# s1mple.net
KiCad netlist of a schematic drawn in Altium Designer
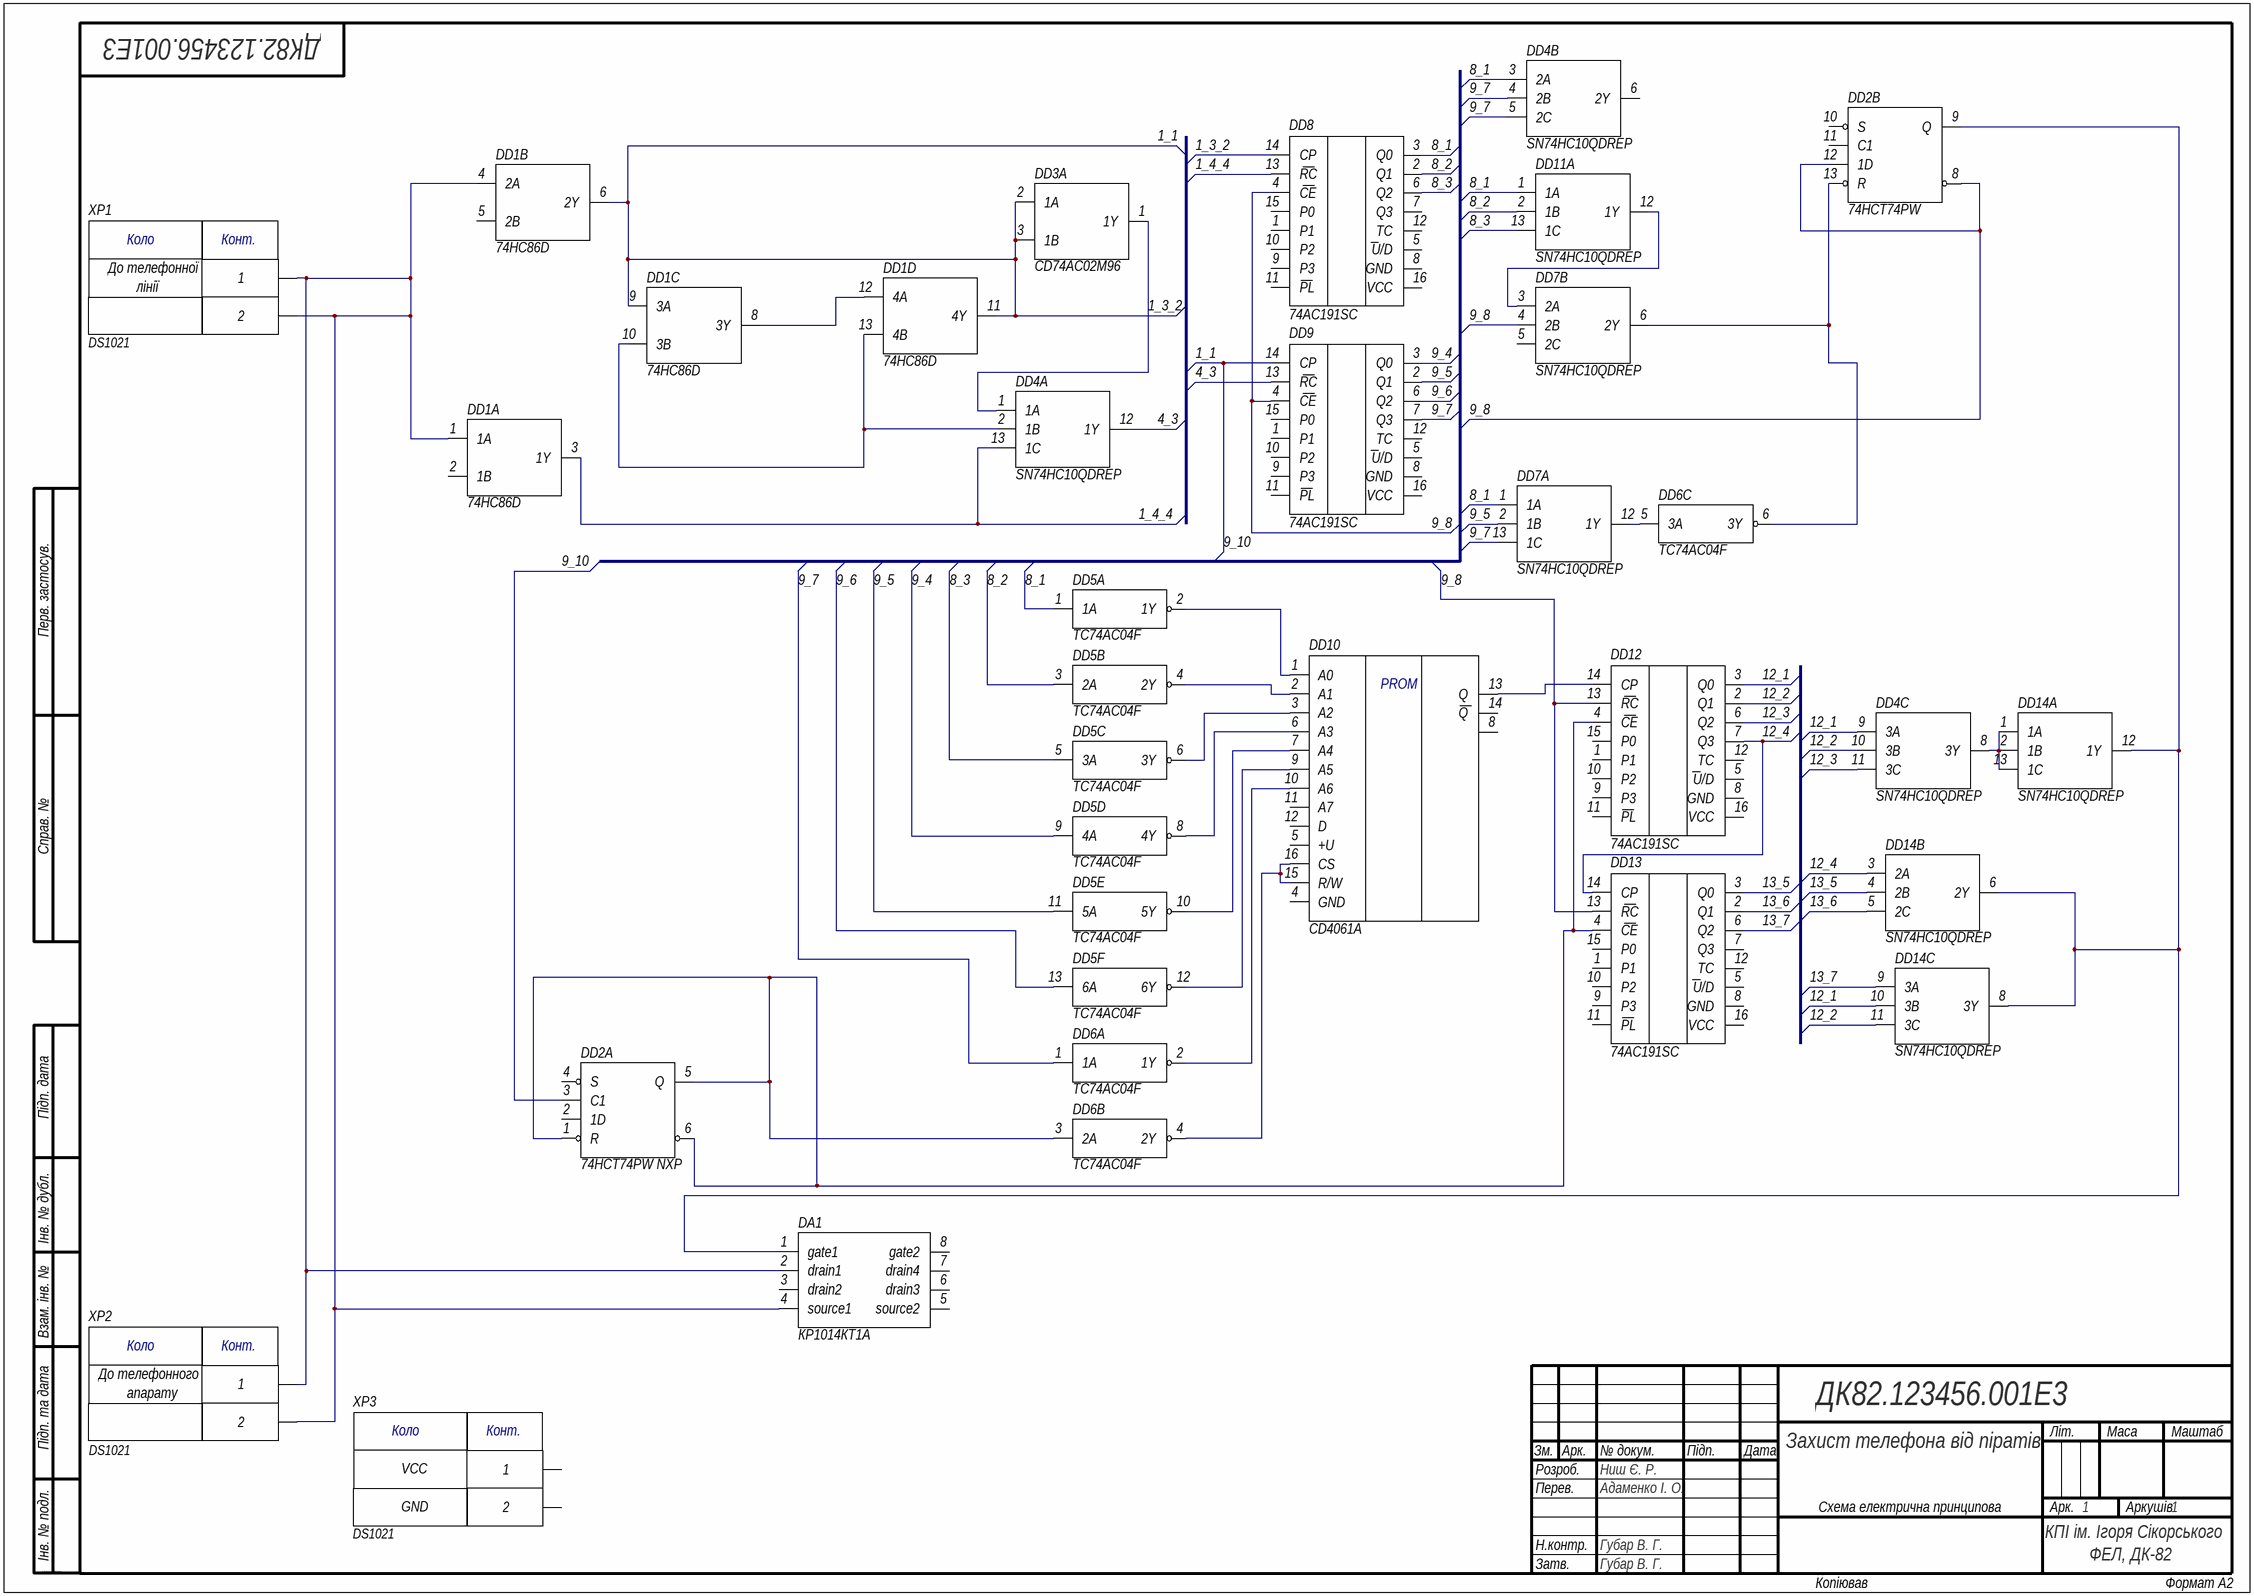
[diagram p0: s1mple.SchDoc]

(export (version "E")
  (design (tool "Eeschema 10.0.6"))
  (components
    (comp (ref "DA1")
      (value "КР1014КТ1А Электроника и связь")
      (footprint "DIP8")
      (fields (field (name "NAME") "КР1014КТ1А") (field (name "MANUFACTURER") "Электроника и связь"))
      (libsource (lib "Schlib1") (part "КР1014КТ1А"))
    )
    (comp (ref "DD1")
      (value "74HC86D Philips")
      (footprint "SOIC-14")
      (description "OR")
      (fields (field (name "NAME") "74HC86D") (field (name "MANUFACTURER") "Philips"))
      (libsource (lib "Schlib1") (part "74HC86D"))
    )
    (comp (ref "DD2")
      (value "74HCT74PW NXP")
      (footprint "TSSOP-14")
      (description "DUAL D FF POSEDG TRIG")
      (fields (field (name "MANUFACTURER") "NXP") (field (name "NAME") "74HCT74PW"))
      (libsource (lib "Schlib1") (part "74HCT74PW"))
    )
    (comp (ref "DD3")
      (value "CD74AC02M96 TI")
      (footprint "SOIC-14")
      (description "2-INPUT NOR GATE")
      (fields (field (name "NAME") "CD74AC02M96") (field (name "MANUFACTURER") "TI"))
      (libsource (lib "Schlib1") (part "CD74AC02M96"))
    )
    (comp (ref "DD4")
      (value "SN74HC10QDREP Texas Instruments")
      (footprint "SOIC-14")
      (description "3-INPUT NAND GATE")
      (fields (field (name "NAME") "SN74HC10QDREP") (field (name "MANUFACTURER") "Texas Instruments"))
      (libsource (lib "Schlib1") (part "SN74HC10QDREP"))
    )
    (comp (ref "DD5")
      (value "TC74AC04F Toshiba")
      (footprint "SOIC-14")
      (description "NOT")
      (fields (field (name "NAME") "TC74AC04F") (field (name "MANUFACTURER") "Toshiba"))
      (libsource (lib "Schlib1") (part "TC74AC04F"))
    )
    (comp (ref "DD6")
      (value "TC74AC04F Toshiba")
      (footprint "SOIC-14")
      (description "NOT")
      (fields (field (name "NAME") "TC74AC04F") (field (name "MANUFACTURER") "Toshiba"))
      (libsource (lib "Schlib1") (part "TC74AC04F"))
    )
    (comp (ref "DD7")
      (value "SN74HC10QDREP Texas Instruments")
      (footprint "SOIC-14")
      (description "3-INPUT NAND GATE")
      (fields (field (name "NAME") "SN74HC10QDREP") (field (name "MANUFACTURER") "Texas Instruments"))
      (libsource (lib "Schlib1") (part "SN74HC10QDREP"))
    )
    (comp (ref "DD8")
      (value "74AC191SC Fairchild")
      (footprint "SOIC-16")
      (description "Counter")
      (fields (field (name "NAME") "74AC191SC") (field (name "MANUFACTURER") "Fairchild"))
      (libsource (lib "Schlib1") (part "74AC191SC"))
    )
    (comp (ref "DD9")
      (value "74AC191SC Fairchild")
      (footprint "SOIC-16")
      (description "Counter")
      (fields (field (name "NAME") "74AC191SC") (field (name "MANUFACTURER") "Fairchild"))
      (libsource (lib "Schlib1") (part "74AC191SC"))
    )
    (comp (ref "DD10")
      (value "CD4061A NXP")
      (footprint "DIP16")
      (fields (field (name "NAME") "CD4061A") (field (name "MANUFACTURER") "NXP"))
      (libsource (lib "Schlib1") (part "CD4061A"))
    )
    (comp (ref "DD11")
      (value "SN74HC10QDREP Texas Instruments")
      (footprint "SOIC-14")
      (description "3-INPUT NAND GATE")
      (fields (field (name "NAME") "SN74HC10QDREP") (field (name "MANUFACTURER") "Texas Instruments"))
      (libsource (lib "Schlib1") (part "SN74HC10QDREP"))
    )
    (comp (ref "DD12")
      (value "74AC191SC Fairchild")
      (footprint "SOIC-16")
      (description "Counter")
      (fields (field (name "NAME") "74AC191SC") (field (name "MANUFACTURER") "Fairchild"))
      (libsource (lib "Schlib1") (part "74AC191SC"))
    )
    (comp (ref "DD13")
      (value "74AC191SC Fairchild")
      (footprint "SOIC-16")
      (description "Counter")
      (fields (field (name "NAME") "74AC191SC") (field (name "MANUFACTURER") "Fairchild"))
      (libsource (lib "Schlib1") (part "74AC191SC"))
    )
    (comp (ref "DD14")
      (value "SN74HC10QDREP Texas Instruments")
      (footprint "SOIC-14")
      (description "3-INPUT NAND GATE")
      (fields (field (name "NAME") "SN74HC10QDREP") (field (name "MANUFACTURER") "Texas Instruments"))
      (libsource (lib "Schlib1") (part "SN74HC10QDREP"))
    )
    (comp (ref "XP1")
      (value "DS1021 Ningbo Zhenqin Electronic")
      (footprint "PLS-2")
      (description "PLS-2_1x2")
      (fields (field (name "MANUFACTURER") "Ningbo Zhenqin Electronic") (field (name "NAME") "DS1021"))
      (libsource (lib "Schlib1") (part "DS1021"))
    )
    (comp (ref "XP2")
      (value "DS1021 Ningbo Zhenqin Electronic")
      (footprint "PLS-2")
      (description "PLS-2_1x2")
      (fields (field (name "MANUFACTURER") "Ningbo Zhenqin Electronic") (field (name "NAME") "DS1021"))
      (libsource (lib "Schlib1") (part "DS1021"))
    )
    (comp (ref "XP3")
      (value "DS1021 Ningbo Zhenqin Electronic")
      (footprint "PLS-2")
      (description "PLS-2_1x2")
      (fields (field (name "MANUFACTURER") "Ningbo Zhenqin Electronic") (field (name "NAME") "DS1021"))
      (libsource (lib "Schlib1") (part "DS1021"))
    )
  )
  (nets
    (net (code "1") (name "/1_1") (class "Default")
      (node (ref "DD1") (pin "11") (pinfunction "4Y_11") (pintype "passive"))
      (node (ref "DD1") (pin "6") (pinfunction "2Y_6") (pintype "passive"))
      (node (ref "DD1") (pin "9") (pinfunction "3A_9") (pintype "passive"))
      (node (ref "DD2") (pin "3") (pinfunction "C1_3") (pintype "passive"))
      (node (ref "DD3") (pin "1") (pinfunction "1Y_1") (pintype "passive"))
      (node (ref "DD3") (pin "2") (pinfunction "1A_2") (pintype "passive"))
      (node (ref "DD3") (pin "3") (pinfunction "1B_3") (pintype "passive"))
      (node (ref "DD4") (pin "1") (pinfunction "1A_1") (pintype "passive"))
      (node (ref "DD8") (pin "14") (pinfunction "CP_14") (pintype "passive"))
      (node (ref "DD9") (pin "14") (pinfunction "CP_14") (pintype "passive"))
    )
    (net (code "2") (name "/1_4_4") (class "Default")
      (node (ref "DD1") (pin "3") (pinfunction "1Y_3") (pintype "passive"))
      (node (ref "DD4") (pin "13") (pinfunction "1C_13") (pintype "passive"))
      (node (ref "DD8") (pin "13") (pinfunction "RC_13") (pintype "passive"))
    )
    (net (code "3") (name "/4_3") (class "Default")
      (node (ref "DD4") (pin "12") (pinfunction "1Y_12") (pintype "passive"))
      (node (ref "DD9") (pin "13") (pinfunction "RC_13") (pintype "passive"))
    )
    (net (code "4") (name "/8_1") (class "Default")
      (node (ref "DD11") (pin "1") (pinfunction "1A_1") (pintype "passive"))
      (node (ref "DD4") (pin "3") (pinfunction "2A_3") (pintype "passive"))
      (node (ref "DD5") (pin "1") (pinfunction "1A_1") (pintype "passive"))
      (node (ref "DD7") (pin "1") (pinfunction "1A_1") (pintype "passive"))
      (node (ref "DD8") (pin "3") (pinfunction "Q0_3") (pintype "passive"))
    )
    (net (code "5") (name "/8_2") (class "Default")
      (node (ref "DD11") (pin "2") (pinfunction "1B_2") (pintype "passive"))
      (node (ref "DD5") (pin "3") (pinfunction "2A_3") (pintype "passive"))
      (node (ref "DD8") (pin "2") (pinfunction "Q1_2") (pintype "passive"))
    )
    (net (code "6") (name "/8_3") (class "Default")
      (node (ref "DD11") (pin "13") (pinfunction "1C_13") (pintype "passive"))
      (node (ref "DD5") (pin "5") (pinfunction "3A_5") (pintype "passive"))
      (node (ref "DD8") (pin "6") (pinfunction "Q2_6") (pintype "passive"))
    )
    (net (code "7") (name "/9_4") (class "Default")
      (node (ref "DD5") (pin "9") (pinfunction "4A_9") (pintype "passive"))
      (node (ref "DD9") (pin "3") (pinfunction "Q0_3") (pintype "passive"))
    )
    (net (code "8") (name "/9_5") (class "Default")
      (node (ref "DD5") (pin "11") (pinfunction "5A_11") (pintype "passive"))
      (node (ref "DD7") (pin "2") (pinfunction "1B_2") (pintype "passive"))
      (node (ref "DD9") (pin "2") (pinfunction "Q1_2") (pintype "passive"))
    )
    (net (code "9") (name "/9_6") (class "Default")
      (node (ref "DD5") (pin "13") (pinfunction "6A_13") (pintype "passive"))
      (node (ref "DD9") (pin "6") (pinfunction "Q2_6") (pintype "passive"))
    )
    (net (code "10") (name "/9_7") (class "Default")
      (node (ref "DD4") (pin "4") (pinfunction "2B_4") (pintype "passive"))
      (node (ref "DD4") (pin "5") (pinfunction "2C_5") (pintype "passive"))
      (node (ref "DD6") (pin "1") (pinfunction "1A_1") (pintype "passive"))
      (node (ref "DD7") (pin "13") (pinfunction "1C_13") (pintype "passive"))
      (node (ref "DD9") (pin "7") (pinfunction "Q3_7") (pintype "passive"))
    )
    (net (code "11") (name "/9_8") (class "Default")
      (node (ref "DD12") (pin "13") (pinfunction "RC_13") (pintype "passive"))
      (node (ref "DD13") (pin "13") (pinfunction "RC_13") (pintype "passive"))
      (node (ref "DD2") (pin "12") (pinfunction "1D_12") (pintype "passive"))
      (node (ref "DD2") (pin "8") (pinfunction "Q_8") (pintype "passive"))
      (node (ref "DD7") (pin "4") (pinfunction "2B_4") (pintype "passive"))
      (node (ref "DD8") (pin "4") (pinfunction "CE_4") (pintype "passive"))
      (node (ref "DD9") (pin "4") (pinfunction "CE_4") (pintype "passive"))
    )
    (net (code "12") (name "/12_1") (class "Default")
      (node (ref "DD12") (pin "3") (pinfunction "Q0_3") (pintype "passive"))
      (node (ref "DD14") (pin "10") (pinfunction "3B_10") (pintype "passive"))
      (node (ref "DD4") (pin "9") (pinfunction "3A_9") (pintype "passive"))
    )
    (net (code "13") (name "/12_2") (class "Default")
      (node (ref "DD12") (pin "2") (pinfunction "Q1_2") (pintype "passive"))
      (node (ref "DD14") (pin "11") (pinfunction "3C_11") (pintype "passive"))
      (node (ref "DD4") (pin "10") (pinfunction "3B_10") (pintype "passive"))
    )
    (net (code "14") (name "/12_3") (class "Default")
      (node (ref "DD12") (pin "6") (pinfunction "Q2_6") (pintype "passive"))
      (node (ref "DD4") (pin "11") (pinfunction "3C_11") (pintype "passive"))
    )
    (net (code "15") (name "/12_4") (class "Default")
      (node (ref "DD12") (pin "7") (pinfunction "Q3_7") (pintype "passive"))
      (node (ref "DD13") (pin "14") (pinfunction "CP_14") (pintype "passive"))
      (node (ref "DD14") (pin "3") (pinfunction "2A_3") (pintype "passive"))
    )
    (net (code "16") (name "/13_5") (class "Default")
      (node (ref "DD13") (pin "3") (pinfunction "Q0_3") (pintype "passive"))
      (node (ref "DD14") (pin "4") (pinfunction "2B_4") (pintype "passive"))
    )
    (net (code "17") (name "/13_6") (class "Default")
      (node (ref "DD13") (pin "2") (pinfunction "Q1_2") (pintype "passive"))
      (node (ref "DD14") (pin "5") (pinfunction "2C_5") (pintype "passive"))
    )
    (net (code "18") (name "/13_7") (class "Default")
      (node (ref "DD13") (pin "6") (pinfunction "Q2_6") (pintype "passive"))
      (node (ref "DD14") (pin "9") (pinfunction "3A_9") (pintype "passive"))
    )
    (net (code "19") (name "Net-(DA1-drain1)") (class "Default")
      (node (ref "DA1") (pin "2") (pinfunction "drain1_2") (pintype "passive"))
      (node (ref "DA1") (pin "4") (pinfunction "source1_4") (pintype "passive"))
      (node (ref "DD1") (pin "1") (pinfunction "1A_1") (pintype "passive"))
      (node (ref "DD1") (pin "4") (pinfunction "2A_4") (pintype "passive"))
      (node (ref "XP1") (pin "1") (pinfunction "1_1") (pintype "passive"))
      (node (ref "XP1") (pin "2") (pinfunction "2_2") (pintype "passive"))
      (node (ref "XP2") (pin "1") (pinfunction "1_1") (pintype "passive"))
      (node (ref "XP2") (pin "2") (pinfunction "2_2") (pintype "passive"))
    )
    (net (code "20") (name "Net-(DA1-gate1)") (class "Default")
      (node (ref "DA1") (pin "1") (pinfunction "gate1_1") (pintype "passive"))
      (node (ref "DD14") (pin "12") (pinfunction "1Y_12") (pintype "passive"))
      (node (ref "DD14") (pin "6") (pinfunction "2Y_6") (pintype "passive"))
      (node (ref "DD14") (pin "8") (pinfunction "3Y_8") (pintype "passive"))
      (node (ref "DD2") (pin "9") (pinfunction "Q_9") (pintype "passive"))
    )
    (net (code "21") (name "Net-(DD1C-3B)") (class "Default")
      (node (ref "DD1") (pin "10") (pinfunction "3B_10") (pintype "passive"))
      (node (ref "DD1") (pin "13") (pinfunction "4B_13") (pintype "passive"))
      (node (ref "DD4") (pin "2") (pinfunction "1B_2") (pintype "passive"))
    )
    (net (code "22") (name "Net-(DD1C-3Y)") (class "Default")
      (node (ref "DD1") (pin "12") (pinfunction "4A_12") (pintype "passive"))
      (node (ref "DD1") (pin "8") (pinfunction "3Y_8") (pintype "passive"))
    )
    (net (code "23") (name "Net-(DD2B-R)") (class "Default")
      (node (ref "DD2") (pin "13") (pinfunction "R_13") (pintype "passive"))
      (node (ref "DD6") (pin "6") (pinfunction "3Y_6") (pintype "passive"))
      (node (ref "DD7") (pin "6") (pinfunction "2Y_6") (pintype "passive"))
    )
    (net (code "24") (name "Net-(DD6C-3A)") (class "Default")
      (node (ref "DD6") (pin "5") (pinfunction "3A_5") (pintype "passive"))
      (node (ref "DD7") (pin "12") (pinfunction "1Y_12") (pintype "passive"))
    )
    (net (code "25") (name "Net-(DD10-A0)") (class "Default")
      (node (ref "DD10") (pin "1") (pinfunction "A0_1") (pintype "passive"))
      (node (ref "DD5") (pin "2") (pinfunction "1Y_2") (pintype "passive"))
    )
    (net (code "26") (name "Net-(DD10-A1)") (class "Default")
      (node (ref "DD10") (pin "2") (pinfunction "A1_2") (pintype "passive"))
      (node (ref "DD5") (pin "4") (pinfunction "2Y_4") (pintype "passive"))
    )
    (net (code "27") (name "Net-(DD10-A2)") (class "Default")
      (node (ref "DD10") (pin "3") (pinfunction "A2_3") (pintype "passive"))
      (node (ref "DD5") (pin "6") (pinfunction "3Y_6") (pintype "passive"))
    )
    (net (code "28") (name "Net-(DD10-A3)") (class "Default")
      (node (ref "DD10") (pin "6") (pinfunction "A3_6") (pintype "passive"))
      (node (ref "DD5") (pin "8") (pinfunction "4Y_8") (pintype "passive"))
    )
    (net (code "29") (name "Net-(DD10-A4)") (class "Default")
      (node (ref "DD10") (pin "7") (pinfunction "A4_7") (pintype "passive"))
      (node (ref "DD5") (pin "10") (pinfunction "5Y_10") (pintype "passive"))
    )
    (net (code "30") (name "Net-(DD10-A5)") (class "Default")
      (node (ref "DD10") (pin "9") (pinfunction "A5_9") (pintype "passive"))
      (node (ref "DD5") (pin "12") (pinfunction "6Y_12") (pintype "passive"))
    )
    (net (code "31") (name "Net-(DD10-A6)") (class "Default")
      (node (ref "DD10") (pin "10") (pinfunction "A6_10") (pintype "passive"))
      (node (ref "DD6") (pin "2") (pinfunction "1Y_2") (pintype "passive"))
    )
    (net (code "32") (name "Net-(DD10-CS)") (class "Default")
      (node (ref "DD10") (pin "15") (pinfunction "R/W_15") (pintype "passive"))
      (node (ref "DD10") (pin "16") (pinfunction "CS_16") (pintype "passive"))
      (node (ref "DD6") (pin "4") (pinfunction "2Y_4") (pintype "passive"))
    )
    (net (code "33") (name "Net-(DD11A-1Y)") (class "Default")
      (node (ref "DD11") (pin "12") (pinfunction "1Y_12") (pintype "passive"))
      (node (ref "DD7") (pin "3") (pinfunction "2A_3") (pintype "passive"))
    )
    (net (code "34") (name "Net-(DD12-CE)") (class "Default")
      (node (ref "DD12") (pin "4") (pinfunction "CE_4") (pintype "passive"))
      (node (ref "DD13") (pin "4") (pinfunction "CE_4") (pintype "passive"))
      (node (ref "DD2") (pin "1") (pinfunction "R_1") (pintype "passive"))
      (node (ref "DD2") (pin "5") (pinfunction "Q_5") (pintype "passive"))
      (node (ref "DD2") (pin "6") (pinfunction "Q_6") (pintype "passive"))
      (node (ref "DD6") (pin "3") (pinfunction "2A_3") (pintype "passive"))
    )
    (net (code "35") (name "Net-(DD12-CP)") (class "Default")
      (node (ref "DD10") (pin "13") (pinfunction "Q_13") (pintype "passive"))
      (node (ref "DD12") (pin "14") (pinfunction "CP_14") (pintype "passive"))
    )
    (net (code "36") (name "Net-(DD14A-1A)") (class "Default")
      (node (ref "DD14") (pin "1") (pinfunction "1A_1") (pintype "passive"))
      (node (ref "DD14") (pin "13") (pinfunction "1C_13") (pintype "passive"))
      (node (ref "DD14") (pin "2") (pinfunction "1B_2") (pintype "passive"))
      (node (ref "DD4") (pin "8") (pinfunction "3Y_8") (pintype "passive"))
    )
    (net (code "37") (name "unconnected-(DA1-drain2-Pad3)") (class "Default")
      (node (ref "DA1") (pin "3") (pinfunction "drain2_3") (pintype "passive"))
    )
    (net (code "38") (name "unconnected-(DA1-drain3-Pad6)") (class "Default")
      (node (ref "DA1") (pin "6") (pinfunction "drain3_6") (pintype "passive"))
    )
    (net (code "39") (name "unconnected-(DA1-drain4-Pad7)") (class "Default")
      (node (ref "DA1") (pin "7") (pinfunction "drain4_7") (pintype "passive"))
    )
    (net (code "40") (name "unconnected-(DA1-gate2-Pad8)") (class "Default")
      (node (ref "DA1") (pin "8") (pinfunction "gate2_8") (pintype "passive"))
    )
    (net (code "41") (name "unconnected-(DA1-source2-Pad5)") (class "Default")
      (node (ref "DA1") (pin "5") (pinfunction "source2_5") (pintype "passive"))
    )
    (net (code "42") (name "unconnected-(DD1A-1B-Pad2)") (class "Default")
      (node (ref "DD1") (pin "2") (pinfunction "1B_2") (pintype "passive"))
    )
    (net (code "43") (name "unconnected-(DD1B-2B-Pad5)") (class "Default")
      (node (ref "DD1") (pin "5") (pinfunction "2B_5") (pintype "passive"))
    )
    (net (code "44") (name "unconnected-(DD2A-1D-Pad2)") (class "Default")
      (node (ref "DD2") (pin "2") (pinfunction "1D_2") (pintype "passive"))
    )
    (net (code "45") (name "unconnected-(DD2A-S-Pad4)") (class "Default")
      (node (ref "DD2") (pin "4") (pinfunction "S_4") (pintype "passive"))
    )
    (net (code "46") (name "unconnected-(DD2B-C1-Pad11)") (class "Default")
      (node (ref "DD2") (pin "11") (pinfunction "C1_11") (pintype "passive"))
    )
    (net (code "47") (name "unconnected-(DD2B-S-Pad10)") (class "Default")
      (node (ref "DD2") (pin "10") (pinfunction "S_10") (pintype "passive"))
    )
    (net (code "48") (name "unconnected-(DD4B-2Y-Pad6)") (class "Default")
      (node (ref "DD4") (pin "6") (pinfunction "2Y_6") (pintype "passive"))
    )
    (net (code "49") (name "unconnected-(DD7B-2C-Pad5)") (class "Default")
      (node (ref "DD7") (pin "5") (pinfunction "2C_5") (pintype "passive"))
    )
    (net (code "50") (name "unconnected-(DD8-GND-Pad8)") (class "Default")
      (node (ref "DD8") (pin "8") (pinfunction "GND_8") (pintype "passive"))
    )
    (net (code "51") (name "unconnected-(DD8-P0-Pad15)") (class "Default")
      (node (ref "DD8") (pin "15") (pinfunction "P0_15") (pintype "passive"))
    )
    (net (code "52") (name "unconnected-(DD8-P1-Pad1)") (class "Default")
      (node (ref "DD8") (pin "1") (pinfunction "P1_1") (pintype "passive"))
    )
    (net (code "53") (name "unconnected-(DD8-P2-Pad10)") (class "Default")
      (node (ref "DD8") (pin "10") (pinfunction "P2_10") (pintype "passive"))
    )
    (net (code "54") (name "unconnected-(DD8-P3-Pad9)") (class "Default")
      (node (ref "DD8") (pin "9") (pinfunction "P3_9") (pintype "passive"))
    )
    (net (code "55") (name "unconnected-(DD8-PL-Pad11)") (class "Default")
      (node (ref "DD8") (pin "11") (pinfunction "PL_11") (pintype "passive"))
    )
    (net (code "56") (name "unconnected-(DD8-Q3-Pad7)") (class "Default")
      (node (ref "DD8") (pin "7") (pinfunction "Q3_7") (pintype "passive"))
    )
    (net (code "57") (name "unconnected-(DD8-TC-Pad12)") (class "Default")
      (node (ref "DD8") (pin "12") (pinfunction "TC_12") (pintype "passive"))
    )
    (net (code "58") (name "unconnected-(DD8-U{slash}D-Pad5)") (class "Default")
      (node (ref "DD8") (pin "5") (pinfunction "U/D_5") (pintype "passive"))
    )
    (net (code "59") (name "unconnected-(DD8-VCC-Pad16)") (class "Default")
      (node (ref "DD8") (pin "16") (pinfunction "VCC_16") (pintype "passive"))
    )
    (net (code "60") (name "unconnected-(DD9-GND-Pad8)") (class "Default")
      (node (ref "DD9") (pin "8") (pinfunction "GND_8") (pintype "passive"))
    )
    (net (code "61") (name "unconnected-(DD9-P0-Pad15)") (class "Default")
      (node (ref "DD9") (pin "15") (pinfunction "P0_15") (pintype "passive"))
    )
    (net (code "62") (name "unconnected-(DD9-P1-Pad1)") (class "Default")
      (node (ref "DD9") (pin "1") (pinfunction "P1_1") (pintype "passive"))
    )
    (net (code "63") (name "unconnected-(DD9-P2-Pad10)") (class "Default")
      (node (ref "DD9") (pin "10") (pinfunction "P2_10") (pintype "passive"))
    )
    (net (code "64") (name "unconnected-(DD9-P3-Pad9)") (class "Default")
      (node (ref "DD9") (pin "9") (pinfunction "P3_9") (pintype "passive"))
    )
    (net (code "65") (name "unconnected-(DD9-PL-Pad11)") (class "Default")
      (node (ref "DD9") (pin "11") (pinfunction "PL_11") (pintype "passive"))
    )
    (net (code "66") (name "unconnected-(DD9-TC-Pad12)") (class "Default")
      (node (ref "DD9") (pin "12") (pinfunction "TC_12") (pintype "passive"))
    )
    (net (code "67") (name "unconnected-(DD9-U{slash}D-Pad5)") (class "Default")
      (node (ref "DD9") (pin "5") (pinfunction "U/D_5") (pintype "passive"))
    )
    (net (code "68") (name "unconnected-(DD9-VCC-Pad16)") (class "Default")
      (node (ref "DD9") (pin "16") (pinfunction "VCC_16") (pintype "passive"))
    )
    (net (code "69") (name "unconnected-(DD10-+U-Pad5)") (class "Default")
      (node (ref "DD10") (pin "5") (pinfunction "+U_5") (pintype "passive"))
    )
    (net (code "70") (name "unconnected-(DD10-A7-Pad11)") (class "Default")
      (node (ref "DD10") (pin "11") (pinfunction "A7_11") (pintype "passive"))
    )
    (net (code "71") (name "unconnected-(DD10-D-Pad12)") (class "Default")
      (node (ref "DD10") (pin "12") (pinfunction "D_12") (pintype "passive"))
    )
    (net (code "72") (name "unconnected-(DD10-GND-Pad4)") (class "Default")
      (node (ref "DD10") (pin "4") (pinfunction "GND_4") (pintype "passive"))
    )
    (net (code "73") (name "unconnected-(DD10-Pad8)") (class "Default")
      (node (ref "DD10") (pin "8") (pintype "passive"))
    )
    (net (code "74") (name "unconnected-(DD10-Q-Pad14)") (class "Default")
      (node (ref "DD10") (pin "14") (pinfunction "Q_14") (pintype "passive"))
    )
    (net (code "75") (name "unconnected-(DD12-GND-Pad8)") (class "Default")
      (node (ref "DD12") (pin "8") (pinfunction "GND_8") (pintype "passive"))
    )
    (net (code "76") (name "unconnected-(DD12-P0-Pad15)") (class "Default")
      (node (ref "DD12") (pin "15") (pinfunction "P0_15") (pintype "passive"))
    )
    (net (code "77") (name "unconnected-(DD12-P1-Pad1)") (class "Default")
      (node (ref "DD12") (pin "1") (pinfunction "P1_1") (pintype "passive"))
    )
    (net (code "78") (name "unconnected-(DD12-P2-Pad10)") (class "Default")
      (node (ref "DD12") (pin "10") (pinfunction "P2_10") (pintype "passive"))
    )
    (net (code "79") (name "unconnected-(DD12-P3-Pad9)") (class "Default")
      (node (ref "DD12") (pin "9") (pinfunction "P3_9") (pintype "passive"))
    )
    (net (code "80") (name "unconnected-(DD12-PL-Pad11)") (class "Default")
      (node (ref "DD12") (pin "11") (pinfunction "PL_11") (pintype "passive"))
    )
    (net (code "81") (name "unconnected-(DD12-TC-Pad12)") (class "Default")
      (node (ref "DD12") (pin "12") (pinfunction "TC_12") (pintype "passive"))
    )
    (net (code "82") (name "unconnected-(DD12-U{slash}D-Pad5)") (class "Default")
      (node (ref "DD12") (pin "5") (pinfunction "U/D_5") (pintype "passive"))
    )
    (net (code "83") (name "unconnected-(DD12-VCC-Pad16)") (class "Default")
      (node (ref "DD12") (pin "16") (pinfunction "VCC_16") (pintype "passive"))
    )
    (net (code "84") (name "unconnected-(DD13-GND-Pad8)") (class "Default")
      (node (ref "DD13") (pin "8") (pinfunction "GND_8") (pintype "passive"))
    )
    (net (code "85") (name "unconnected-(DD13-P0-Pad15)") (class "Default")
      (node (ref "DD13") (pin "15") (pinfunction "P0_15") (pintype "passive"))
    )
    (net (code "86") (name "unconnected-(DD13-P1-Pad1)") (class "Default")
      (node (ref "DD13") (pin "1") (pinfunction "P1_1") (pintype "passive"))
    )
    (net (code "87") (name "unconnected-(DD13-P2-Pad10)") (class "Default")
      (node (ref "DD13") (pin "10") (pinfunction "P2_10") (pintype "passive"))
    )
    (net (code "88") (name "unconnected-(DD13-P3-Pad9)") (class "Default")
      (node (ref "DD13") (pin "9") (pinfunction "P3_9") (pintype "passive"))
    )
    (net (code "89") (name "unconnected-(DD13-PL-Pad11)") (class "Default")
      (node (ref "DD13") (pin "11") (pinfunction "PL_11") (pintype "passive"))
    )
    (net (code "90") (name "unconnected-(DD13-Q3-Pad7)") (class "Default")
      (node (ref "DD13") (pin "7") (pinfunction "Q3_7") (pintype "passive"))
    )
    (net (code "91") (name "unconnected-(DD13-TC-Pad12)") (class "Default")
      (node (ref "DD13") (pin "12") (pinfunction "TC_12") (pintype "passive"))
    )
    (net (code "92") (name "unconnected-(DD13-U{slash}D-Pad5)") (class "Default")
      (node (ref "DD13") (pin "5") (pinfunction "U/D_5") (pintype "passive"))
    )
    (net (code "93") (name "unconnected-(DD13-VCC-Pad16)") (class "Default")
      (node (ref "DD13") (pin "16") (pinfunction "VCC_16") (pintype "passive"))
    )
    (net (code "94") (name "unconnected-(XP3-Pad1)") (class "Default")
      (node (ref "XP3") (pin "1") (pinfunction "1_1") (pintype "passive"))
    )
    (net (code "95") (name "unconnected-(XP3-Pad2)") (class "Default")
      (node (ref "XP3") (pin "2") (pinfunction "2_2") (pintype "passive"))
    )
  )
)
